# Sheet2.net
KiCad netlist of a schematic drawn in Altium Designer
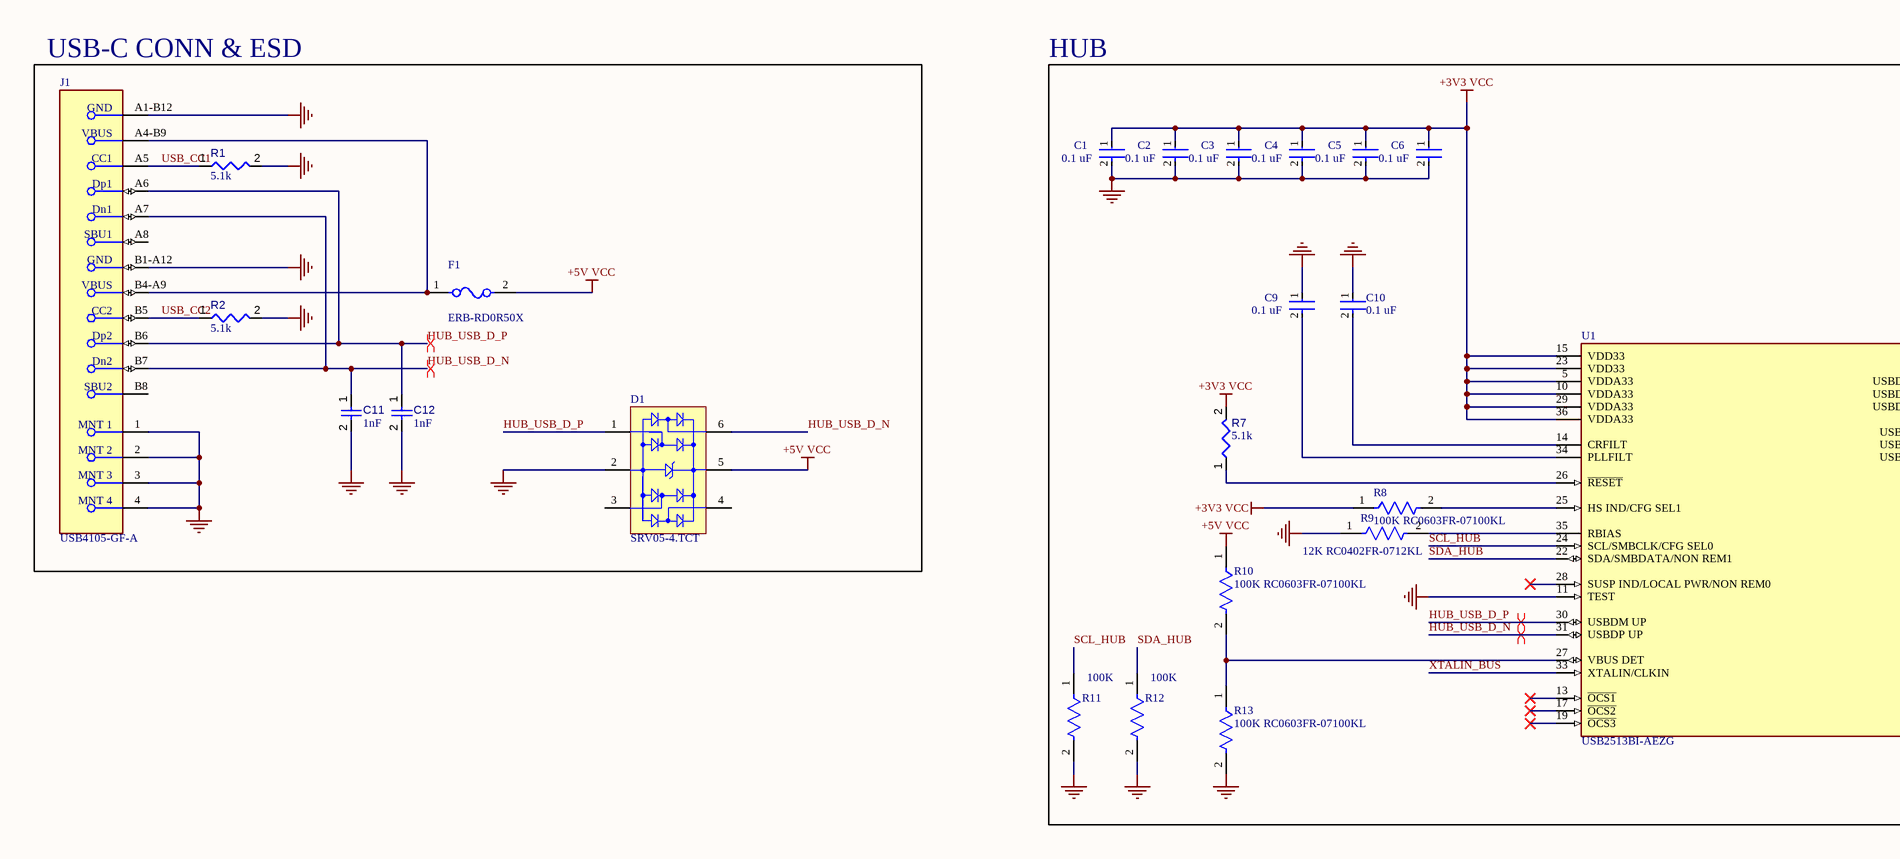
[diagram p0: Sheet2.SchDoc, left]
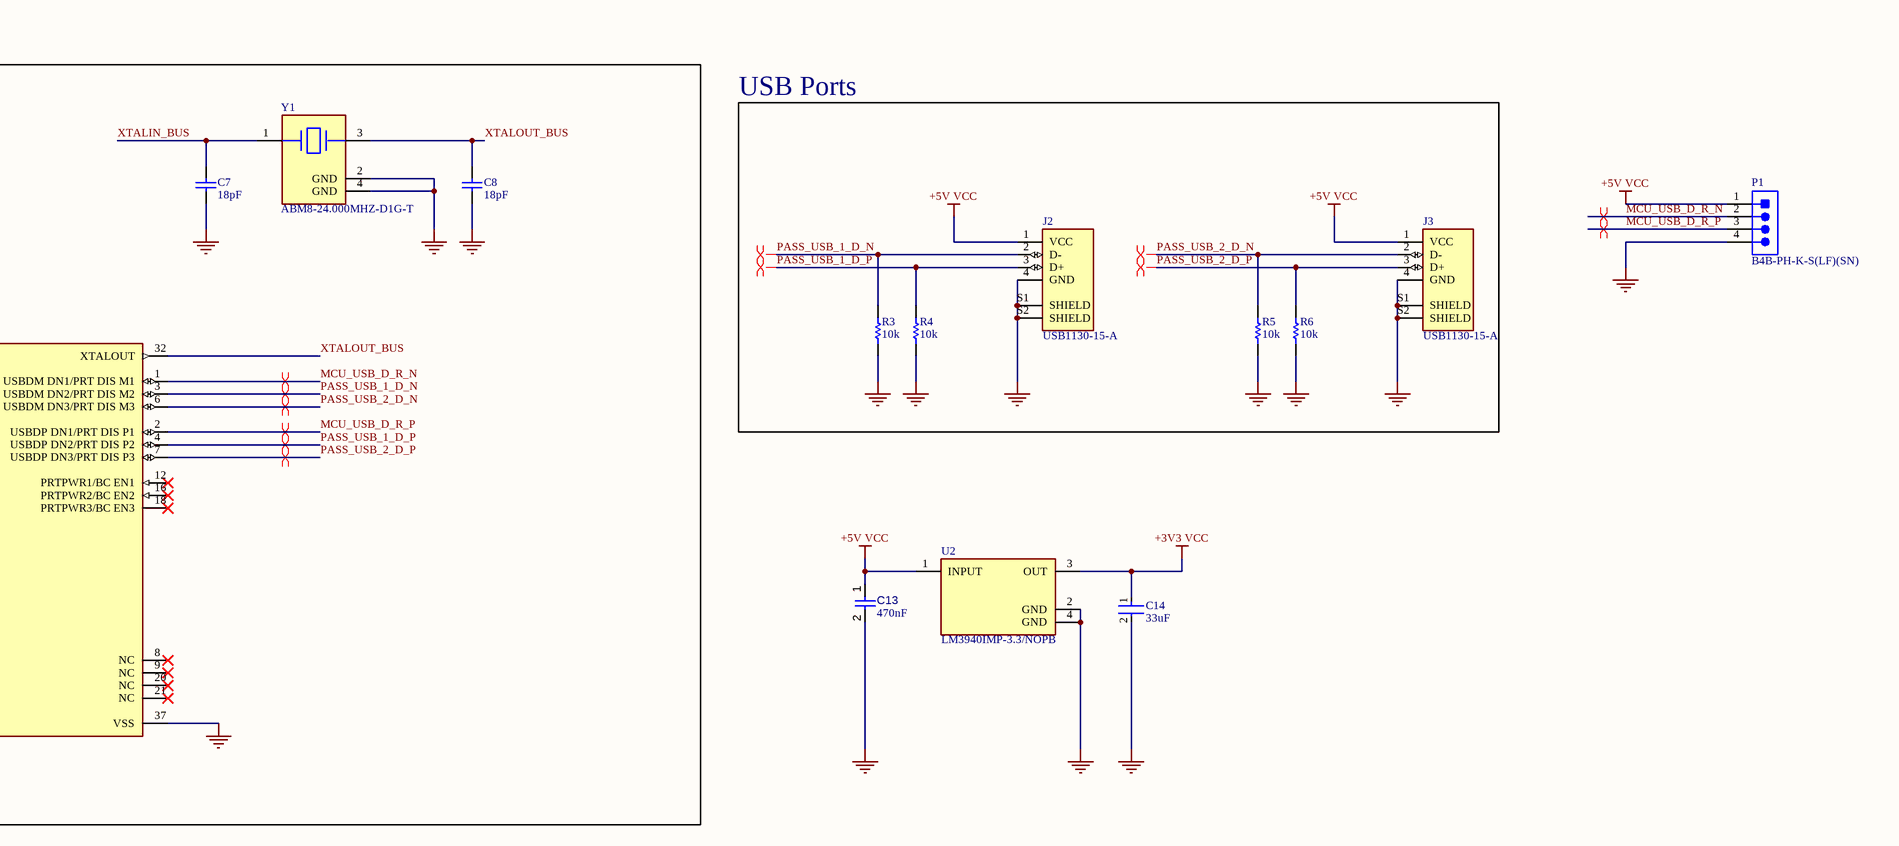
[diagram p1: Sheet2.SchDoc, right]

(export (version "E")
  (design (tool "Eeschema 10.0.6"))
  (components
    (comp (ref "C1")
      (value "0.1 uF")
      (footprint "FP-GRM15-MFG")
      (description "CAP CER 0.1UF 16V X7R 0402\r\n GRM155R71C104KA88D")
      (fields (field (name "MANUFACTURER PART NUMBER") "GRM155R71C104KA88D") (field (name "TOLERANCE") "10%"))
      (libsource (lib "Altium Content Vault") (part "236180d848d6139a670b325ea6854c9"))
    )
    (comp (ref "C2")
      (value "0.1 uF")
      (footprint "FP-GRM15-MFG")
      (description "CAP CER 0.1UF 16V X7R 0402\r\n GRM155R71C104KA88D")
      (fields (field (name "MANUFACTURER PART NUMBER") "GRM155R71C104KA88D") (field (name "TOLERANCE") "10%"))
      (libsource (lib "Altium Content Vault") (part "236180d848d6139a670b325ea6854c9"))
    )
    (comp (ref "C3")
      (value "0.1 uF")
      (footprint "FP-GRM15-MFG")
      (description "CAP CER 0.1UF 16V X7R 0402\r\n GRM155R71C104KA88D")
      (fields (field (name "MANUFACTURER PART NUMBER") "GRM155R71C104KA88D") (field (name "TOLERANCE") "10%"))
      (libsource (lib "Altium Content Vault") (part "236180d848d6139a670b325ea6854c9"))
    )
    (comp (ref "C4")
      (value "0.1 uF")
      (footprint "FP-GRM15-MFG")
      (description "CAP CER 0.1UF 16V X7R 0402\r\n GRM155R71C104KA88D")
      (fields (field (name "MANUFACTURER PART NUMBER") "GRM155R71C104KA88D") (field (name "TOLERANCE") "10%"))
      (libsource (lib "Altium Content Vault") (part "236180d848d6139a670b325ea6854c9"))
    )
    (comp (ref "C5")
      (value "0.1 uF")
      (footprint "FP-GRM15-MFG")
      (description "CAP CER 0.1UF 16V X7R 0402\r\n GRM155R71C104KA88D")
      (fields (field (name "MANUFACTURER PART NUMBER") "GRM155R71C104KA88D") (field (name "TOLERANCE") "10%"))
      (libsource (lib "Altium Content Vault") (part "236180d848d6139a670b325ea6854c9"))
    )
    (comp (ref "C6")
      (value "0.1 uF")
      (footprint "FP-GRM15-MFG")
      (description "CAP CER 0.1UF 16V X7R 0402\r\n GRM155R71C104KA88D")
      (fields (field (name "MANUFACTURER PART NUMBER") "GRM155R71C104KA88D") (field (name "TOLERANCE") "10%"))
      (libsource (lib "Altium Content Vault") (part "236180d848d6139a670b325ea6854c9"))
    )
    (comp (ref "C7")
      (value "18pF")
      (footprint "CAPC1608X90X35LL10T15")
      (fields (field (name "TOLERANCE") "±5%") (field (name "MANUFACTURER") "Murata"))
      (libsource (lib "Altium Content Vault") (part "CAP-NP-2"))
    )
    (comp (ref "C8")
      (value "18pF")
      (footprint "CAPC1608X90X35LL10T15")
      (fields (field (name "TOLERANCE") "±5%") (field (name "MANUFACTURER") "Murata"))
      (libsource (lib "Altium Content Vault") (part "CAP-NP-2"))
    )
    (comp (ref "C9")
      (value "0.1 uF")
      (footprint "FP-GRM15-MFG")
      (description "CAP CER 0.1UF 16V X7R 0402\r\n GRM155R71C104KA88D")
      (fields (field (name "MANUFACTURER PART NUMBER") "GRM155R71C104KA88D") (field (name "TOLERANCE") "10%"))
      (libsource (lib "Altium Content Vault") (part "236180d848d6139a670b325ea6854c9"))
    )
    (comp (ref "C10")
      (value "0.1 uF")
      (footprint "FP-GRM15-MFG")
      (description "CAP CER 0.1UF 16V X7R 0402")
      (fields (field (name "MANUFACTURER PART NUMBER") "GRM155R71C104KA88D") (field (name "TOLERANCE") "10%"))
      (libsource (lib "Altium Content Vault") (part "236180d848d6139a670b325ea6854c9"))
    )
    (comp (ref "C11")
      (value "1nF")
      (footprint "CAPC0402(1005)33_L")
      (description "Chip Capacitor, 1nF +/-20%, 50V, 0402, Thickness 0.33 mm")
      (fields (field (name "TOLERANCE") "10%") (field (name "Comment") "Capacitor 1nF +/-20% 50V 0402"))
      (libsource (lib "Pennsylvania State University") (part "CAP-NP-2"))
    )
    (comp (ref "C12")
      (value "1nF")
      (footprint "CAPC0402(1005)33_L")
      (description "Chip Capacitor, 1nF +/-20%, 50V, 0402, Thickness 0.33 mm")
      (fields (field (name "TOLERANCE") "10%") (field (name "Comment") "Capacitor 1nF +/-20% 50V 0402"))
      (libsource (lib "Pennsylvania State University") (part "CAP-NP-2"))
    )
    (comp (ref "C13")
      (value "470nF")
      (footprint "CAPC0603(1608)100_L")
      (description "Chip Capacitor, 470nF +/-20%, 25V, 0603, Thickness 1 mm")
      (fields (field (name "TOLERANCE") "10%") (field (name "Comment") "Capacitor 470nF +/-20% 25V 0603"))
      (libsource (lib "Pennsylvania State University") (part "CAP-NP-2"))
    )
    (comp (ref "C14")
      (value "33uF")
      (footprint "FP-C2012-125-0_2-IPC_A")
      (description "Multilayer Ceramic Capacitors 33μF ±20% 6.3V X5R SMD 0805\r\nC2012X5R0J336M125AC")
      (fields (field (name "TOLERANCE") "20%"))
      (libsource (lib "Altium Content Vault") (part "b4654b650e69147ec39a6b967a45e02"))
    )
    (comp (ref "D1")
      (value "SRV05-4.TCT")
      (footprint "SMTC-SOT23-6_V")
      (fields (field (name "MANUFACTURER") "Semtech"))
      (libsource (lib "Altium Content Vault") (part "STM-USB_DVI_HDMIULC6-4SC6X-SOT23-6L"))
    )
    (comp (ref "F1")
      (value "ERB-RD0R50X")
      (footprint "FP-ERBRD-MFG")
      (description "FUSE BOARD MNT 500MA 32VDC 0402")
      (fields
        (field (name "MANUFACTURER") "Panasonic Electronic Components")
        (field (name "OCTOPART") "https://octopart.com/erb-rd0r50x-panasonic-21220527")
      )
      (libsource (lib "Altium Content Vault") (part "5bcf9b9f640e542cf0359d10258e979"))
    )
    (comp (ref "J1")
      (value "USB4105-GF-A")
      (footprint "FP-USB4105-GF-A-MFG")
      (libsource (lib "Pennsylvania State University") (part "e7c17a616881a82b79941196b4bec10"))
    )
    (comp (ref "J2")
      (value "USB1130-15-A")
      (footprint "GCT_USB1130-15-A_REVA")
      (fields (field (name "MF") "Global Connector Technology"))
      (libsource (lib "Pennsylvania State University") (part "USB1130-15-A_REVA"))
    )
    (comp (ref "J3")
      (value "USB1130-15-A")
      (footprint "GCT_USB1130-15-A_REVA")
      (fields (field (name "MF") "Global Connector Technology"))
      (libsource (lib "Pennsylvania State University") (part "USB1130-15-A_REVA"))
    )
    (comp (ref "P1")
      (value "B4B-PH-K-S(LF)(SN)")
      (footprint "JST-B4B-PH-K-S_V")
      (fields (field (name "MANUFACTURER") "JST"))
      (libsource (lib "Altium Content Vault") (part "CN-1P-M-R4"))
    )
    (comp (ref "R1")
      (value "5.1k")
      (footprint "RESC1005X40X25NL05T10")
      (fields
        (field (name "TOLERANCE") "1%")
        (field (name "POWER") "62.5mW")
        (field (name "Comment") "RC0402FR-075K1L")
      )
      (libsource (lib "Pennsylvania State University") (part "RES-2"))
    )
    (comp (ref "R2")
      (value "5.1k")
      (footprint "RESC1005X40X25NL05T10")
      (fields
        (field (name "TOLERANCE") "1%")
        (field (name "POWER") "62.5mW")
        (field (name "Comment") "RC0402FR-075K1L")
      )
      (libsource (lib "Pennsylvania State University") (part "RES-2"))
    )
    (comp (ref "R3")
      (value "10k")
      (footprint "RESC1005X40X25ML05T05")
      (description "ERJ-2GEJ103X\r\n10kohm resistor")
      (fields (field (name "PART NUMBER") "ERJ-2GEJ103X") (field (name "MANUFACTURER") "Panasonic"))
      (libsource (lib "Altium Content Vault") (part "RES"))
    )
    (comp (ref "R4")
      (value "10k")
      (footprint "RESC1005X40X25ML05T05")
      (description "ERJ-2GEJ103X\r\n10kohm resistor")
      (fields (field (name "PART NUMBER") "ERJ-2GEJ103X") (field (name "MANUFACTURER") "Panasonic"))
      (libsource (lib "Altium Content Vault") (part "RES"))
    )
    (comp (ref "R5")
      (value "10k")
      (footprint "RESC1005X40X25ML05T05")
      (description "ERJ-2GEJ103X\r\n10kohm resistor")
      (fields (field (name "PART NUMBER") "ERJ-2GEJ103X") (field (name "MANUFACTURER") "Panasonic"))
      (libsource (lib "Altium Content Vault") (part "RES"))
    )
    (comp (ref "R6")
      (value "10k")
      (footprint "RESC1005X40X25ML05T05")
      (description "ERJ-2GEJ103X\r\n10kohm resistor")
      (fields (field (name "PART NUMBER") "ERJ-2GEJ103X") (field (name "MANUFACTURER") "Panasonic"))
      (libsource (lib "Altium Content Vault") (part "RES"))
    )
    (comp (ref "R7")
      (value "5.1k")
      (footprint "RESC1005X40X25NL05T10")
      (fields
        (field (name "TOLERANCE") "1%")
        (field (name "POWER") "62.5mW")
        (field (name "Comment") "RC0402FR-075K1L")
      )
      (libsource (lib "Pennsylvania State University") (part "RES-2"))
    )
    (comp (ref "R8")
      (value "100K RC0603FR-07100KL")
      (footprint "FP-RC0603-0_55-MFG")
      (description "RES SMD 100K OHM 1% 1/10W 0603")
      (fields (field (name "TOLERANCE") "1%"))
      (libsource (lib "Altium Content Vault") (part "1029c3af85768c4190bb7ad29bc67b5"))
    )
    (comp (ref "R9")
      (value "12K RC0402FR-0712KL")
      (footprint "FP-RC0402-0_4-IPC_C")
      (description "RES SMD 12K OHM 1% 1/16W 0402")
      (fields (field (name "TOLERANCE") "1%"))
      (libsource (lib "Altium Content Vault") (part "1029c3af85768c4190bb7ad29bc67b5"))
    )
    (comp (ref "R10")
      (value "100K RC0603FR-07100KL")
      (footprint "FP-RC0603-0_55-MFG")
      (description "RES SMD 100K OHM 1% 1/10W 0603")
      (fields (field (name "TOLERANCE") "1%"))
      (libsource (lib "Altium Content Vault") (part "1029c3af85768c4190bb7ad29bc67b5"))
    )
    (comp (ref "R11")
      (value "100K")
      (footprint "FP-RC0603-0_55-MFG")
      (description "RES SMD 100K OHM 1% 1/10W 0603")
      (fields (field (name "TOLERANCE") "1%"))
      (libsource (lib "Altium Content Vault") (part "1029c3af85768c4190bb7ad29bc67b5"))
    )
    (comp (ref "R12")
      (value "100K")
      (footprint "FP-RC0603-0_55-MFG")
      (description "RES SMD 100K OHM 1% 1/10W 0603")
      (fields (field (name "TOLERANCE") "1%"))
      (libsource (lib "Altium Content Vault") (part "1029c3af85768c4190bb7ad29bc67b5"))
    )
    (comp (ref "R13")
      (value "100K RC0603FR-07100KL")
      (footprint "FP-RC0603-0_55-MFG")
      (description "RES SMD 100K OHM 1% 1/10W 0603")
      (fields (field (name "TOLERANCE") "1%"))
      (libsource (lib "Altium Content Vault") (part "1029c3af85768c4190bb7ad29bc67b5"))
    )
    (comp (ref "U1")
      (value "USB2513BI-AEZG")
      (footprint "FP-USB2513BI-AEZG-MFG")
      (description "IC USB 2.0 3PORT HUB CTLR 36QFN")
      (fields
        (field (name "OCTOPART") "https://octopart.com/usb2513bi-aezg-microchip-24995419")
        (field (name "MANUFACTURER") "Microchip")
      )
      (libsource (lib "Altium Content Vault") (part "984e6bd26c3cb98b9c3c36886b8b675"))
    )
    (comp (ref "U2")
      (value "LM3940IMP-3.3/NOPB")
      (footprint "FP-DCY0004A-MFG")
      (description "IC REG LINEAR 3.3V 1A SOT223-4")
      (libsource (lib "Altium Content Vault") (part "ef78896361455d16e3252a05c23564e"))
    )
    (comp (ref "Y1")
      (value "ABM8-24.000MHZ-D1G-T")
      (footprint "FP-ABM8-MFG")
      (description "Crystal 24MHz ±10ppm 18pF SMD-4 3.2mm x 2.5mm")
      (libsource (lib "Altium Content Vault") (part "dfdb7f9a12507849fb681da9a70121c"))
    )
  )
  (nets
    (net (code "1") (name "+3V3 VCC") (class "Default")
      (node (ref "C1") (pin "1") (pinfunction "1_1") (pintype "passive"))
      (node (ref "C14") (pin "1") (pinfunction "1_1") (pintype "passive"))
      (node (ref "C2") (pin "1") (pinfunction "1_1") (pintype "passive"))
      (node (ref "C3") (pin "1") (pinfunction "1_1") (pintype "passive"))
      (node (ref "C4") (pin "1") (pinfunction "1_1") (pintype "passive"))
      (node (ref "C5") (pin "1") (pinfunction "1_1") (pintype "passive"))
      (node (ref "C6") (pin "1") (pinfunction "1_1") (pintype "passive"))
      (node (ref "R7") (pin "2") (pinfunction "2_2") (pintype "passive"))
      (node (ref "R8") (pin "1") (pinfunction "1_1") (pintype "passive"))
      (node (ref "U1") (pin "10") (pinfunction "VDDA33_10") (pintype "power_in"))
      (node (ref "U1") (pin "15") (pinfunction "VDD33_15") (pintype "power_in"))
      (node (ref "U1") (pin "23") (pinfunction "VDD33_23") (pintype "power_in"))
      (node (ref "U1") (pin "29") (pinfunction "VDDA33_29") (pintype "power_in"))
      (node (ref "U1") (pin "36") (pinfunction "VDDA33_36") (pintype "power_in"))
      (node (ref "U1") (pin "5") (pinfunction "VDDA33_5") (pintype "power_in"))
      (node (ref "U2") (pin "3") (pinfunction "OUT_3") (pintype "power_in"))
    )
    (net (code "2") (name "+5V VCC") (class "Default")
      (node (ref "C13") (pin "1") (pinfunction "1_1") (pintype "passive"))
      (node (ref "D1") (pin "5") (pinfunction "VBUS_5") (pintype "passive"))
      (node (ref "F1") (pin "2") (pinfunction "2_2") (pintype "passive"))
      (node (ref "J2") (pin "1") (pinfunction "VCC_1") (pintype "power_in"))
      (node (ref "J3") (pin "1") (pinfunction "VCC_1") (pintype "power_in"))
      (node (ref "P1") (pin "1") (pinfunction "1_1") (pintype "passive"))
      (node (ref "R10") (pin "1") (pinfunction "1_1") (pintype "passive"))
      (node (ref "U2") (pin "1") (pinfunction "INPUT_1") (pintype "power_in"))
    )
    (net (code "3") (name "/HUB_USB_D_N") (class "Default")
      (node (ref "C11") (pin "1") (pinfunction "1_1") (pintype "passive"))
      (node (ref "D1") (pin "6") (pinfunction "I/O_4_6") (pintype "passive"))
      (node (ref "J1") (pin "A7") (pinfunction "Dn1_A7") (pintype "bidirectional"))
      (node (ref "J1") (pin "B7") (pinfunction "Dn2_B7") (pintype "bidirectional"))
      (node (ref "U1") (pin "31") (pinfunction "USBDP_UP_31") (pintype "bidirectional"))
    )
    (net (code "4") (name "/HUB_USB_D_P") (class "Default")
      (node (ref "C12") (pin "1") (pinfunction "1_1") (pintype "passive"))
      (node (ref "D1") (pin "1") (pinfunction "I/O_1_1") (pintype "passive"))
      (node (ref "J1") (pin "A6") (pinfunction "Dp1_A6") (pintype "bidirectional"))
      (node (ref "J1") (pin "B6") (pinfunction "Dp2_B6") (pintype "bidirectional"))
      (node (ref "U1") (pin "30") (pinfunction "USBDM_UP_30") (pintype "bidirectional"))
    )
    (net (code "5") (name "/MCU_USB_D_R_N") (class "Default")
      (node (ref "P1") (pin "2") (pinfunction "2_2") (pintype "passive"))
      (node (ref "U1") (pin "1") (pinfunction "USBDM_DN1/PRT_DIS_M1_1") (pintype "bidirectional"))
    )
    (net (code "6") (name "/MCU_USB_D_R_P") (class "Default")
      (node (ref "P1") (pin "3") (pinfunction "3_3") (pintype "passive"))
      (node (ref "U1") (pin "2") (pinfunction "USBDP_DN1/PRT_DIS_P1_2") (pintype "bidirectional"))
    )
    (net (code "7") (name "/PASS_USB_1_D_N") (class "Default")
      (node (ref "J2") (pin "2") (pinfunction "D-_2") (pintype "bidirectional"))
      (node (ref "R3") (pin "2") (pinfunction "2_2") (pintype "passive"))
      (node (ref "U1") (pin "3") (pinfunction "USBDM_DN2/PRT_DIS_M2_3") (pintype "bidirectional"))
    )
    (net (code "8") (name "/PASS_USB_1_D_P") (class "Default")
      (node (ref "J2") (pin "3") (pinfunction "D+_3") (pintype "bidirectional"))
      (node (ref "R4") (pin "2") (pinfunction "2_2") (pintype "passive"))
      (node (ref "U1") (pin "4") (pinfunction "USBDP_DN2/PRT_DIS_P2_4") (pintype "bidirectional"))
    )
    (net (code "9") (name "/PASS_USB_2_D_N") (class "Default")
      (node (ref "J3") (pin "2") (pinfunction "D-_2") (pintype "bidirectional"))
      (node (ref "R5") (pin "2") (pinfunction "2_2") (pintype "passive"))
      (node (ref "U1") (pin "6") (pinfunction "USBDM_DN3/PRT_DIS_M3_6") (pintype "bidirectional"))
    )
    (net (code "10") (name "/PASS_USB_2_D_P") (class "Default")
      (node (ref "J3") (pin "3") (pinfunction "D+_3") (pintype "bidirectional"))
      (node (ref "R6") (pin "2") (pinfunction "2_2") (pintype "passive"))
      (node (ref "U1") (pin "7") (pinfunction "USBDP_DN3/PRT_DIS_P3_7") (pintype "bidirectional"))
    )
    (net (code "11") (name "/SCL_HUB") (class "Default")
      (node (ref "R11") (pin "1") (pinfunction "1_1") (pintype "passive"))
      (node (ref "U1") (pin "24") (pinfunction "SCL/SMBCLK/CFG_SEL0_24") (pintype "input"))
    )
    (net (code "12") (name "/SDA_HUB") (class "Default")
      (node (ref "R12") (pin "1") (pinfunction "1_1") (pintype "passive"))
      (node (ref "U1") (pin "22") (pinfunction "SDA/SMBDATA/NON_REM1_22") (pintype "bidirectional"))
    )
    (net (code "13") (name "/USB_CC1") (class "Default")
      (node (ref "J1") (pin "A5") (pinfunction "CC1_A5") (pintype "power_in"))
      (node (ref "R1") (pin "1") (pinfunction "1_1") (pintype "passive"))
    )
    (net (code "14") (name "/USB_CC2") (class "Default")
      (node (ref "J1") (pin "B5") (pinfunction "CC2_B5") (pintype "bidirectional"))
      (node (ref "R2") (pin "1") (pinfunction "1_1") (pintype "passive"))
    )
    (net (code "15") (name "/XTALIN_BUS") (class "Default")
      (node (ref "C7") (pin "2") (pinfunction "2_2") (pintype "passive"))
      (node (ref "U1") (pin "33") (pinfunction "XTALIN/CLKIN_33") (pintype "input"))
      (node (ref "Y1") (pin "1") (pinfunction "1_1") (pintype "passive"))
    )
    (net (code "16") (name "/XTALOUT_BUS") (class "Default")
      (node (ref "C8") (pin "2") (pinfunction "2_2") (pintype "passive"))
      (node (ref "U1") (pin "32") (pinfunction "XTALOUT_32") (pintype "output"))
      (node (ref "Y1") (pin "3") (pinfunction "3_3") (pintype "passive"))
    )
    (net (code "17") (name "GND") (class "Default")
      (node (ref "C1") (pin "2") (pinfunction "2_2") (pintype "passive"))
      (node (ref "C10") (pin "1") (pinfunction "1_1") (pintype "passive"))
      (node (ref "C11") (pin "2") (pinfunction "2_2") (pintype "passive"))
      (node (ref "C12") (pin "2") (pinfunction "2_2") (pintype "passive"))
      (node (ref "C13") (pin "2") (pinfunction "2_2") (pintype "passive"))
      (node (ref "C14") (pin "2") (pinfunction "2_2") (pintype "passive"))
      (node (ref "C2") (pin "2") (pinfunction "2_2") (pintype "passive"))
      (node (ref "C3") (pin "2") (pinfunction "2_2") (pintype "passive"))
      (node (ref "C4") (pin "2") (pinfunction "2_2") (pintype "passive"))
      (node (ref "C5") (pin "2") (pinfunction "2_2") (pintype "passive"))
      (node (ref "C6") (pin "2") (pinfunction "2_2") (pintype "passive"))
      (node (ref "C7") (pin "1") (pinfunction "1_1") (pintype "passive"))
      (node (ref "C8") (pin "1") (pinfunction "1_1") (pintype "passive"))
      (node (ref "C9") (pin "1") (pinfunction "1_1") (pintype "passive"))
      (node (ref "D1") (pin "2") (pinfunction "GND_2") (pintype "passive"))
      (node (ref "J1") (pin "1") (pinfunction "MNT_1_1") (pintype "power_in"))
      (node (ref "J1") (pin "2") (pinfunction "MNT_2_2") (pintype "power_in"))
      (node (ref "J1") (pin "3") (pinfunction "MNT_3_3") (pintype "power_in"))
      (node (ref "J1") (pin "4") (pinfunction "MNT_4_4") (pintype "power_in"))
      (node (ref "J1") (pin "A1-B12") (pinfunction "GND_A1-B12") (pintype "power_in"))
      (node (ref "J1") (pin "B1-A12") (pinfunction "GND_B1-A12") (pintype "bidirectional"))
      (node (ref "J2") (pin "4") (pinfunction "GND_4") (pintype "power_in"))
      (node (ref "J2") (pin "S1") (pinfunction "SHIELD_S1") (pintype "passive"))
      (node (ref "J2") (pin "S2") (pinfunction "SHIELD_S2") (pintype "passive"))
      (node (ref "J3") (pin "4") (pinfunction "GND_4") (pintype "power_in"))
      (node (ref "J3") (pin "S1") (pinfunction "SHIELD_S1") (pintype "passive"))
      (node (ref "J3") (pin "S2") (pinfunction "SHIELD_S2") (pintype "passive"))
      (node (ref "P1") (pin "4") (pinfunction "4_4") (pintype "passive"))
      (node (ref "R1") (pin "2") (pinfunction "2_2") (pintype "passive"))
      (node (ref "R11") (pin "2") (pinfunction "2_2") (pintype "passive"))
      (node (ref "R12") (pin "2") (pinfunction "2_2") (pintype "passive"))
      (node (ref "R13") (pin "2") (pinfunction "2_2") (pintype "passive"))
      (node (ref "R2") (pin "2") (pinfunction "2_2") (pintype "passive"))
      (node (ref "R3") (pin "1") (pinfunction "1_1") (pintype "passive"))
      (node (ref "R4") (pin "1") (pinfunction "1_1") (pintype "passive"))
      (node (ref "R5") (pin "1") (pinfunction "1_1") (pintype "passive"))
      (node (ref "R6") (pin "1") (pinfunction "1_1") (pintype "passive"))
      (node (ref "R9") (pin "1") (pinfunction "1_1") (pintype "passive"))
      (node (ref "U1") (pin "11") (pinfunction "TEST_11") (pintype "input"))
      (node (ref "U1") (pin "37") (pinfunction "VSS_37") (pintype "power_in"))
      (node (ref "U2") (pin "2") (pinfunction "GND_2") (pintype "power_in"))
      (node (ref "U2") (pin "4") (pinfunction "GND_4") (pintype "power_in"))
      (node (ref "Y1") (pin "2") (pinfunction "GND_2") (pintype "power_in"))
      (node (ref "Y1") (pin "4") (pinfunction "GND_4") (pintype "power_in"))
    )
    (net (code "18") (name "Net-(F1-Pad1)") (class "Default")
      (node (ref "F1") (pin "1") (pinfunction "1_1") (pintype "passive"))
      (node (ref "J1") (pin "A4-B9") (pinfunction "VBUS_A4-B9") (pintype "power_in"))
      (node (ref "J1") (pin "B4-A9") (pinfunction "VBUS_B4-A9") (pintype "bidirectional"))
    )
    (net (code "19") (name "Net-(U1-CRFILT)") (class "Default")
      (node (ref "C10") (pin "2") (pinfunction "2_2") (pintype "passive"))
      (node (ref "U1") (pin "14") (pinfunction "CRFILT_14") (pintype "passive"))
    )
    (net (code "20") (name "Net-(U1-HS_IND{slash}CFG_SEL1)") (class "Default")
      (node (ref "R8") (pin "2") (pinfunction "2_2") (pintype "passive"))
      (node (ref "U1") (pin "25") (pinfunction "HS_IND/CFG_SEL1_25") (pintype "input"))
    )
    (net (code "21") (name "Net-(U1-PLLFILT)") (class "Default")
      (node (ref "C9") (pin "2") (pinfunction "2_2") (pintype "passive"))
      (node (ref "U1") (pin "34") (pinfunction "PLLFILT_34") (pintype "passive"))
    )
    (net (code "22") (name "Net-(U1-RBIAS)") (class "Default")
      (node (ref "R9") (pin "2") (pinfunction "2_2") (pintype "passive"))
      (node (ref "U1") (pin "35") (pinfunction "RBIAS_35") (pintype "passive"))
    )
    (net (code "23") (name "Net-(U1-VBUS_DET)") (class "Default")
      (node (ref "R10") (pin "2") (pinfunction "2_2") (pintype "passive"))
      (node (ref "R13") (pin "1") (pinfunction "1_1") (pintype "passive"))
      (node (ref "U1") (pin "27") (pinfunction "VBUS_DET_27") (pintype "bidirectional"))
    )
    (net (code "24") (name "Net-(U1-~{RESET})") (class "Default")
      (node (ref "R7") (pin "1") (pinfunction "1_1") (pintype "passive"))
      (node (ref "U1") (pin "26") (pinfunction "~{RESET}_26") (pintype "input"))
    )
    (net (code "25") (name "unconnected-(D1-I{slash}O_2-Pad3)") (class "Default")
      (node (ref "D1") (pin "3") (pinfunction "I/O_2_3") (pintype "passive"))
    )
    (net (code "26") (name "unconnected-(D1-I{slash}O_3-Pad4)") (class "Default")
      (node (ref "D1") (pin "4") (pinfunction "I/O_3_4") (pintype "passive"))
    )
    (net (code "27") (name "unconnected-(J1-SBU1-PadA8)") (class "Default")
      (node (ref "J1") (pin "A8") (pinfunction "SBU1_A8") (pintype "bidirectional"))
    )
    (net (code "28") (name "unconnected-(J1-SBU2-PadB8)") (class "Default")
      (node (ref "J1") (pin "B8") (pinfunction "SBU2_B8") (pintype "power_in"))
    )
    (net (code "29") (name "unconnected-(U1-NC-Pad8)") (class "Default")
      (node (ref "U1") (pin "8") (pinfunction "NC_8") (pintype "passive+no_connect"))
    )
    (net (code "30") (name "unconnected-(U1-NC-Pad9)") (class "Default")
      (node (ref "U1") (pin "9") (pinfunction "NC_9") (pintype "passive+no_connect"))
    )
    (net (code "31") (name "unconnected-(U1-NC-Pad20)") (class "Default")
      (node (ref "U1") (pin "20") (pinfunction "NC_20") (pintype "passive+no_connect"))
    )
    (net (code "32") (name "unconnected-(U1-NC-Pad21)") (class "Default")
      (node (ref "U1") (pin "21") (pinfunction "NC_21") (pintype "passive+no_connect"))
    )
    (net (code "33") (name "unconnected-(U1-PRTPWR1{slash}BC_EN1-Pad12)") (class "Default")
      (node (ref "U1") (pin "12") (pinfunction "PRTPWR1/BC_EN1_12") (pintype "input+no_connect"))
    )
    (net (code "34") (name "unconnected-(U1-PRTPWR2{slash}BC_EN2-Pad16)") (class "Default")
      (node (ref "U1") (pin "16") (pinfunction "PRTPWR2/BC_EN2_16") (pintype "input+no_connect"))
    )
    (net (code "35") (name "unconnected-(U1-PRTPWR3{slash}BC_EN3-Pad18)") (class "Default")
      (node (ref "U1") (pin "18") (pinfunction "PRTPWR3/BC_EN3_18") (pintype "passive+no_connect"))
    )
    (net (code "36") (name "unconnected-(U1-SUSP_IND{slash}LOCAL_PWR{slash}NON_REM0-Pad28)") (class "Default")
      (node (ref "U1") (pin "28") (pinfunction "SUSP_IND/LOCAL_PWR/NON_REM0_28") (pintype "input+no_connect"))
    )
    (net (code "37") (name "unconnected-(U1-~{OCS1}-Pad13)") (class "Default")
      (node (ref "U1") (pin "13") (pinfunction "~{OCS1}_13") (pintype "input+no_connect"))
    )
    (net (code "38") (name "unconnected-(U1-~{OCS2}-Pad17)") (class "Default")
      (node (ref "U1") (pin "17") (pinfunction "~{OCS2}_17") (pintype "input+no_connect"))
    )
    (net (code "39") (name "unconnected-(U1-~{OCS3}-Pad19)") (class "Default")
      (node (ref "U1") (pin "19") (pinfunction "~{OCS3}_19") (pintype "input+no_connect"))
    )
  )
)
